# baballe.net
KiCad netlist of a schematic drawn in EAGLE
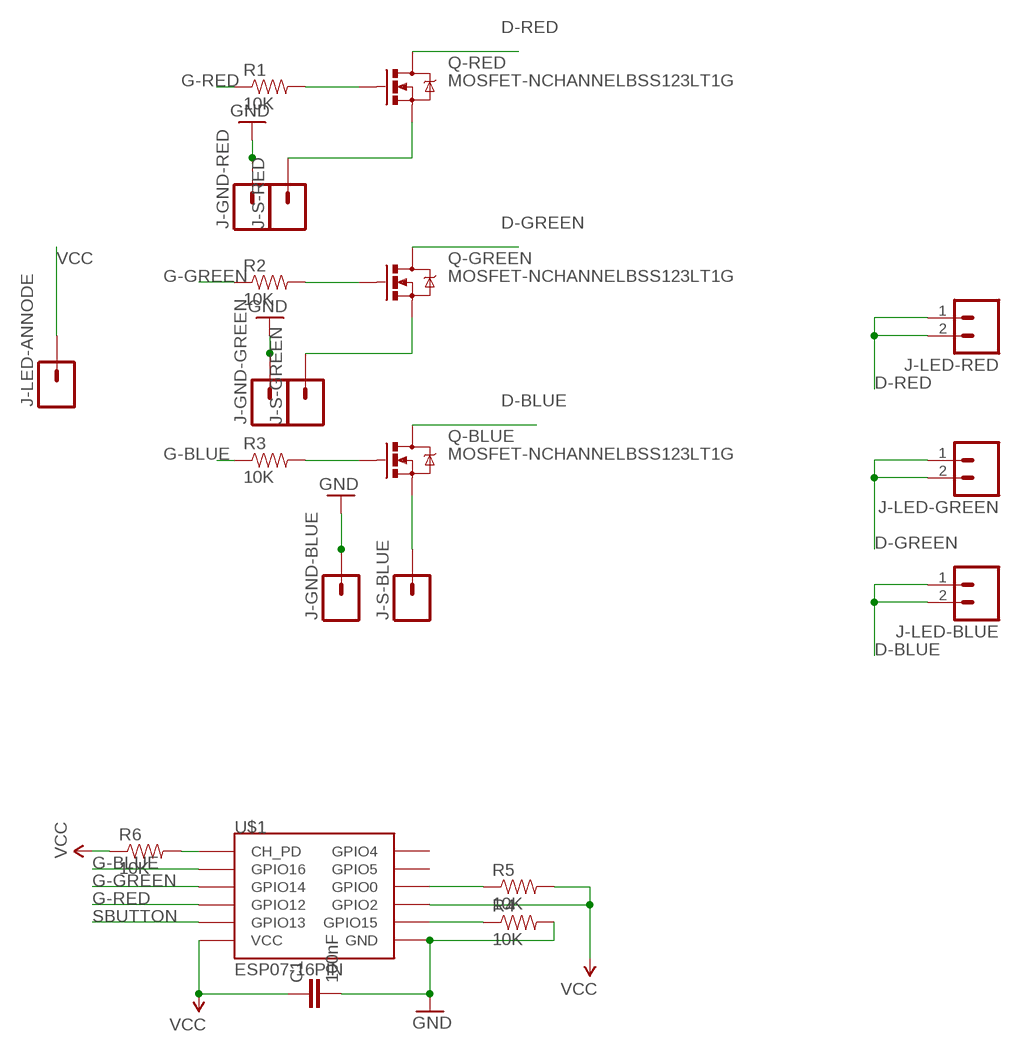
[diagram p0: schematic, sheet 1]

(export (version "E")
  (design (tool "Eeschema 10.0.6"))
  (components
    (comp (ref "C1")
      (value "100nF")
      (footprint "eagle-import:0805")
      (libsource (lib "eagle-import") (part "CAP0805"))
    )
    (comp (ref "J-GND-BLUE")
      (value "M01PTH")
      (footprint "eagle-import:1X01")
      (libsource (lib "eagle-import") (part "M01PTH"))
    )
    (comp (ref "J-GND-GREEN")
      (value "M01PTH")
      (footprint "eagle-import:1X01")
      (libsource (lib "eagle-import") (part "M01PTH"))
    )
    (comp (ref "J-GND-RED")
      (value "M01PTH")
      (footprint "eagle-import:1X01")
      (libsource (lib "eagle-import") (part "M01PTH"))
    )
    (comp (ref "J-LED-ANNODE")
      (value "M01")
      (footprint "eagle-import:1X01-SMALL")
      (libsource (lib "eagle-import") (part "M01"))
    )
    (comp (ref "J-LED-BLUE")
      (value "M02")
      (footprint "eagle-import:1X02_SQUARE")
      (libsource (lib "eagle-import") (part "M02"))
    )
    (comp (ref "J-LED-GREEN")
      (value "M02")
      (footprint "eagle-import:1X02_SQUARE")
      (libsource (lib "eagle-import") (part "M02"))
    )
    (comp (ref "J-LED-RED")
      (value "M02")
      (footprint "eagle-import:1X02_SQUARE")
      (libsource (lib "eagle-import") (part "M02"))
    )
    (comp (ref "J-S-BLUE")
      (value "M01PTH")
      (footprint "eagle-import:1X01")
      (libsource (lib "eagle-import") (part "M01PTH"))
    )
    (comp (ref "J-S-GREEN")
      (value "M01PTH")
      (footprint "eagle-import:1X01")
      (libsource (lib "eagle-import") (part "M01PTH"))
    )
    (comp (ref "J-S-RED")
      (value "M01PTH")
      (footprint "eagle-import:1X01")
      (libsource (lib "eagle-import") (part "M01PTH"))
    )
    (comp (ref "Q-BLUE")
      (value "MOSFET-NCHANNELBSS123LT1G")
      (footprint "eagle-import:SOT23-3")
      (libsource (lib "eagle-import") (part "MOSFET-NCHANNELBSS123LT1G"))
    )
    (comp (ref "Q-GREEN")
      (value "MOSFET-NCHANNELBSS123LT1G")
      (footprint "eagle-import:SOT23-3")
      (libsource (lib "eagle-import") (part "MOSFET-NCHANNELBSS123LT1G"))
    )
    (comp (ref "Q-RED")
      (value "MOSFET-NCHANNELBSS123LT1G")
      (footprint "eagle-import:SOT23-3")
      (libsource (lib "eagle-import") (part "MOSFET-NCHANNELBSS123LT1G"))
    )
    (comp (ref "R1")
      (value "10K")
      (footprint "eagle-import:0805")
      (libsource (lib "eagle-import") (part "RESISTOR0805-RES"))
    )
    (comp (ref "R2")
      (value "10K")
      (footprint "eagle-import:0805")
      (libsource (lib "eagle-import") (part "RESISTOR0805-RES"))
    )
    (comp (ref "R3")
      (value "10K")
      (footprint "eagle-import:0805")
      (libsource (lib "eagle-import") (part "RESISTOR0805-RES"))
    )
    (comp (ref "R4")
      (value "10K")
      (footprint "eagle-import:0805")
      (libsource (lib "eagle-import") (part "RESISTOR0805-RES"))
    )
    (comp (ref "R5")
      (value "10K")
      (footprint "eagle-import:0805")
      (libsource (lib "eagle-import") (part "RESISTOR0805-RES"))
    )
    (comp (ref "R6")
      (value "10K")
      (footprint "eagle-import:0805")
      (libsource (lib "eagle-import") (part "RESISTOR0805-RES"))
    )
    (comp (ref "U$1")
      (value "ESP07-16PIN")
      (footprint "eagle-import:ESP07-16PIN")
      (libsource (lib "eagle-import") (part "ESP07-16PIN"))
    )
  )
  (nets
    (net (code "1") (name "/D-BLUE") (class "Default")
      (node (ref "J-LED-BLUE") (pin "1") (pinfunction "1_1") (pintype "passive"))
      (node (ref "J-LED-BLUE") (pin "2") (pinfunction "2_2") (pintype "passive"))
      (node (ref "Q-BLUE") (pin "3") (pinfunction "D_3") (pintype "passive"))
    )
    (net (code "2") (name "/D-GREEN") (class "Default")
      (node (ref "J-LED-GREEN") (pin "1") (pinfunction "1_1") (pintype "passive"))
      (node (ref "J-LED-GREEN") (pin "2") (pinfunction "2_2") (pintype "passive"))
      (node (ref "Q-GREEN") (pin "3") (pinfunction "D_3") (pintype "passive"))
    )
    (net (code "3") (name "/D-RED") (class "Default")
      (node (ref "J-LED-RED") (pin "1") (pinfunction "1_1") (pintype "passive"))
      (node (ref "J-LED-RED") (pin "2") (pinfunction "2_2") (pintype "passive"))
      (node (ref "Q-RED") (pin "3") (pinfunction "D_3") (pintype "passive"))
    )
    (net (code "4") (name "/G-BLUE") (class "Default")
      (node (ref "R3") (pin "1") (pinfunction "1_1") (pintype "passive"))
      (node (ref "U$1") (pin "GPIO16") (pinfunction "GPIO16_GPIO16") (pintype "bidirectional"))
    )
    (net (code "5") (name "/G-GREEN") (class "Default")
      (node (ref "R2") (pin "1") (pinfunction "1_1") (pintype "passive"))
      (node (ref "U$1") (pin "GPIO14") (pinfunction "GPIO14_GPIO14") (pintype "bidirectional"))
    )
    (net (code "6") (name "/G-RED") (class "Default")
      (node (ref "R1") (pin "1") (pinfunction "1_1") (pintype "passive"))
      (node (ref "U$1") (pin "GPIO12") (pinfunction "GPIO12_GPIO12") (pintype "bidirectional"))
    )
    (net (code "7") (name "/SBUTTON") (class "Default")
      (node (ref "U$1") (pin "GPIO13") (pinfunction "GPIO13_GPIO13") (pintype "bidirectional"))
    )
    (net (code "8") (name "GND") (class "Default")
      (node (ref "C1") (pin "2") (pinfunction "2_2") (pintype "passive"))
      (node (ref "J-GND-BLUE") (pin "1") (pinfunction "1_1") (pintype "passive"))
      (node (ref "J-GND-GREEN") (pin "1") (pinfunction "1_1") (pintype "passive"))
      (node (ref "J-GND-RED") (pin "1") (pinfunction "1_1") (pintype "passive"))
      (node (ref "R4") (pin "2") (pinfunction "2_2") (pintype "passive"))
      (node (ref "U$1") (pin "GND") (pinfunction "GND_GND") (pintype "bidirectional"))
    )
    (net (code "9") (name "Net-(Q-BLUE-G)") (class "Default")
      (node (ref "Q-BLUE") (pin "1") (pinfunction "G_1") (pintype "passive"))
      (node (ref "R3") (pin "2") (pinfunction "2_2") (pintype "passive"))
    )
    (net (code "10") (name "Net-(Q-BLUE-S)") (class "Default")
      (node (ref "J-S-BLUE") (pin "1") (pinfunction "1_1") (pintype "passive"))
      (node (ref "Q-BLUE") (pin "2") (pinfunction "S_2") (pintype "passive"))
    )
    (net (code "11") (name "Net-(Q-GREEN-G)") (class "Default")
      (node (ref "Q-GREEN") (pin "1") (pinfunction "G_1") (pintype "passive"))
      (node (ref "R2") (pin "2") (pinfunction "2_2") (pintype "passive"))
    )
    (net (code "12") (name "Net-(Q-GREEN-S)") (class "Default")
      (node (ref "J-S-GREEN") (pin "1") (pinfunction "1_1") (pintype "passive"))
      (node (ref "Q-GREEN") (pin "2") (pinfunction "S_2") (pintype "passive"))
    )
    (net (code "13") (name "Net-(Q-RED-G)") (class "Default")
      (node (ref "Q-RED") (pin "1") (pinfunction "G_1") (pintype "passive"))
      (node (ref "R1") (pin "2") (pinfunction "2_2") (pintype "passive"))
    )
    (net (code "14") (name "Net-(Q-RED-S)") (class "Default")
      (node (ref "J-S-RED") (pin "1") (pinfunction "1_1") (pintype "passive"))
      (node (ref "Q-RED") (pin "2") (pinfunction "S_2") (pintype "passive"))
    )
    (net (code "15") (name "Net-(R4-Pad1)") (class "Default")
      (node (ref "R4") (pin "1") (pinfunction "1_1") (pintype "passive"))
      (node (ref "U$1") (pin "GPIO15") (pinfunction "GPIO15_GPIO15") (pintype "bidirectional"))
    )
    (net (code "16") (name "Net-(R5-Pad1)") (class "Default")
      (node (ref "R5") (pin "1") (pinfunction "1_1") (pintype "passive"))
      (node (ref "U$1") (pin "GPIO0") (pinfunction "GPIO0_GPIO0") (pintype "bidirectional"))
    )
    (net (code "17") (name "Net-(R6-Pad2)") (class "Default")
      (node (ref "R6") (pin "2") (pinfunction "2_2") (pintype "passive"))
      (node (ref "U$1") (pin "CH_PD") (pinfunction "CH_PD_CH_PD") (pintype "bidirectional"))
    )
    (net (code "18") (name "VCC") (class "Default")
      (node (ref "C1") (pin "1") (pinfunction "1_1") (pintype "passive"))
      (node (ref "J-LED-ANNODE") (pin "1") (pinfunction "1_1") (pintype "passive"))
      (node (ref "R5") (pin "2") (pinfunction "2_2") (pintype "passive"))
      (node (ref "R6") (pin "1") (pinfunction "1_1") (pintype "passive"))
      (node (ref "U$1") (pin "GPIO2") (pinfunction "GPIO2_GPIO2") (pintype "bidirectional"))
      (node (ref "U$1") (pin "VCC") (pinfunction "VCC_VCC") (pintype "bidirectional"))
    )
    (net (code "19") (name "unconnected-(U$1-PadGPIO4)") (class "Default")
      (node (ref "U$1") (pin "GPIO4") (pinfunction "GPIO4_GPIO4") (pintype "bidirectional"))
    )
    (net (code "20") (name "unconnected-(U$1-PadGPIO5)") (class "Default")
      (node (ref "U$1") (pin "GPIO5") (pinfunction "GPIO5_GPIO5") (pintype "bidirectional"))
    )
  )
)
